# XBeeBreakOut.net
KiCad netlist of a schematic drawn in EAGLE
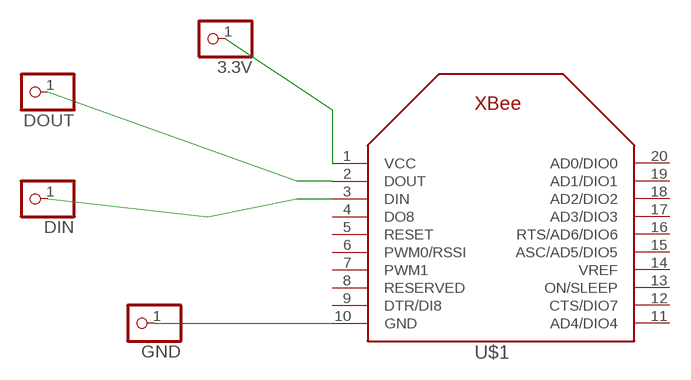
[diagram p0: schematic, sheet 1]

(export (version "E")
  (design (tool "Eeschema 10.0.6"))
  (components
    (comp (ref "3.3V")
      (value "PINHD-1X1")
      (footprint "eagle-import:1X01")
      (libsource (lib "eagle-import") (part "PINHD-1X1"))
    )
    (comp (ref "DIN")
      (value "PINHD-1X1")
      (footprint "eagle-import:1X01")
      (libsource (lib "eagle-import") (part "PINHD-1X1"))
    )
    (comp (ref "DOUT")
      (value "PINHD-1X1")
      (footprint "eagle-import:1X01")
      (libsource (lib "eagle-import") (part "PINHD-1X1"))
    )
    (comp (ref "GND")
      (value "PINHD-1X1")
      (footprint "eagle-import:1X01")
      (libsource (lib "eagle-import") (part "PINHD-1X1"))
    )
    (comp (ref "U$1")
      (value "XBEE")
      (footprint "eagle-import:XBEE")
      (libsource (lib "eagle-import") (part "XBEE"))
    )
  )
  (nets
    (net (code "1") (name "Net-(U$1-DIN)") (class "Default")
      (node (ref "DIN") (pin "1") (pinfunction "1_1") (pintype "passive"))
      (node (ref "U$1") (pin "3") (pinfunction "DIN_3") (pintype "input"))
    )
    (net (code "2") (name "Net-(U$1-DOUT)") (class "Default")
      (node (ref "DOUT") (pin "1") (pinfunction "1_1") (pintype "passive"))
      (node (ref "U$1") (pin "2") (pinfunction "DOUT_2") (pintype "output"))
    )
    (net (code "3") (name "Net-(U$1-GND)") (class "Default")
      (node (ref "GND") (pin "1") (pinfunction "1_1") (pintype "passive"))
      (node (ref "U$1") (pin "10") (pinfunction "GND_10") (pintype "power_in"))
    )
    (net (code "4") (name "Net-(U$1-VCC)") (class "Default")
      (node (ref "3.3V") (pin "1") (pinfunction "1_1") (pintype "passive"))
      (node (ref "U$1") (pin "1") (pinfunction "VCC_1") (pintype "power_in"))
    )
    (net (code "5") (name "unconnected-(U$1-AD0{slash}DIO0-Pad20)") (class "Default")
      (node (ref "U$1") (pin "20") (pinfunction "AD0/DIO0_20") (pintype "bidirectional"))
    )
    (net (code "6") (name "unconnected-(U$1-AD1{slash}DIO1-Pad19)") (class "Default")
      (node (ref "U$1") (pin "19") (pinfunction "AD1/DIO1_19") (pintype "bidirectional"))
    )
    (net (code "7") (name "unconnected-(U$1-AD2{slash}DIO2-Pad18)") (class "Default")
      (node (ref "U$1") (pin "18") (pinfunction "AD2/DIO2_18") (pintype "bidirectional"))
    )
    (net (code "8") (name "unconnected-(U$1-AD3{slash}DIO3-Pad17)") (class "Default")
      (node (ref "U$1") (pin "17") (pinfunction "AD3/DIO3_17") (pintype "bidirectional"))
    )
    (net (code "9") (name "unconnected-(U$1-AD4{slash}DIO4-Pad11)") (class "Default")
      (node (ref "U$1") (pin "11") (pinfunction "AD4/DIO4_11") (pintype "bidirectional"))
    )
    (net (code "10") (name "unconnected-(U$1-ASC{slash}AD5{slash}DIO5-Pad15)") (class "Default")
      (node (ref "U$1") (pin "15") (pinfunction "ASC/AD5/DIO5_15") (pintype "bidirectional"))
    )
    (net (code "11") (name "unconnected-(U$1-CTS{slash}DIO7-Pad12)") (class "Default")
      (node (ref "U$1") (pin "12") (pinfunction "CTS/DIO7_12") (pintype "bidirectional"))
    )
    (net (code "12") (name "unconnected-(U$1-DO8-Pad4)") (class "Default")
      (node (ref "U$1") (pin "4") (pinfunction "DO8_4") (pintype "output"))
    )
    (net (code "13") (name "unconnected-(U$1-DTR{slash}DI8-Pad9)") (class "Default")
      (node (ref "U$1") (pin "9") (pinfunction "DTR/DI8_9") (pintype "input"))
    )
    (net (code "14") (name "unconnected-(U$1-ON{slash}SLEEP-Pad13)") (class "Default")
      (node (ref "U$1") (pin "13") (pinfunction "ON/SLEEP_13") (pintype "output"))
    )
    (net (code "15") (name "unconnected-(U$1-PWM0{slash}RSSI-Pad6)") (class "Default")
      (node (ref "U$1") (pin "6") (pinfunction "PWM0/RSSI_6") (pintype "output"))
    )
    (net (code "16") (name "unconnected-(U$1-PWM1-Pad7)") (class "Default")
      (node (ref "U$1") (pin "7") (pinfunction "PWM1_7") (pintype "output"))
    )
    (net (code "17") (name "unconnected-(U$1-RESERVED-Pad8)") (class "Default")
      (node (ref "U$1") (pin "8") (pinfunction "RESERVED_8") (pintype "no_connect"))
    )
    (net (code "18") (name "unconnected-(U$1-RESET-Pad5)") (class "Default")
      (node (ref "U$1") (pin "5") (pinfunction "RESET_5") (pintype "input"))
    )
    (net (code "19") (name "unconnected-(U$1-RTS{slash}AD6{slash}DIO6-Pad16)") (class "Default")
      (node (ref "U$1") (pin "16") (pinfunction "RTS/AD6/DIO6_16") (pintype "bidirectional"))
    )
    (net (code "20") (name "unconnected-(U$1-VREF-Pad14)") (class "Default")
      (node (ref "U$1") (pin "14") (pinfunction "VREF_14") (pintype "input"))
    )
  )
)
